# 3_ESC_BOARD.net
KiCad netlist of a schematic drawn in EAGLE
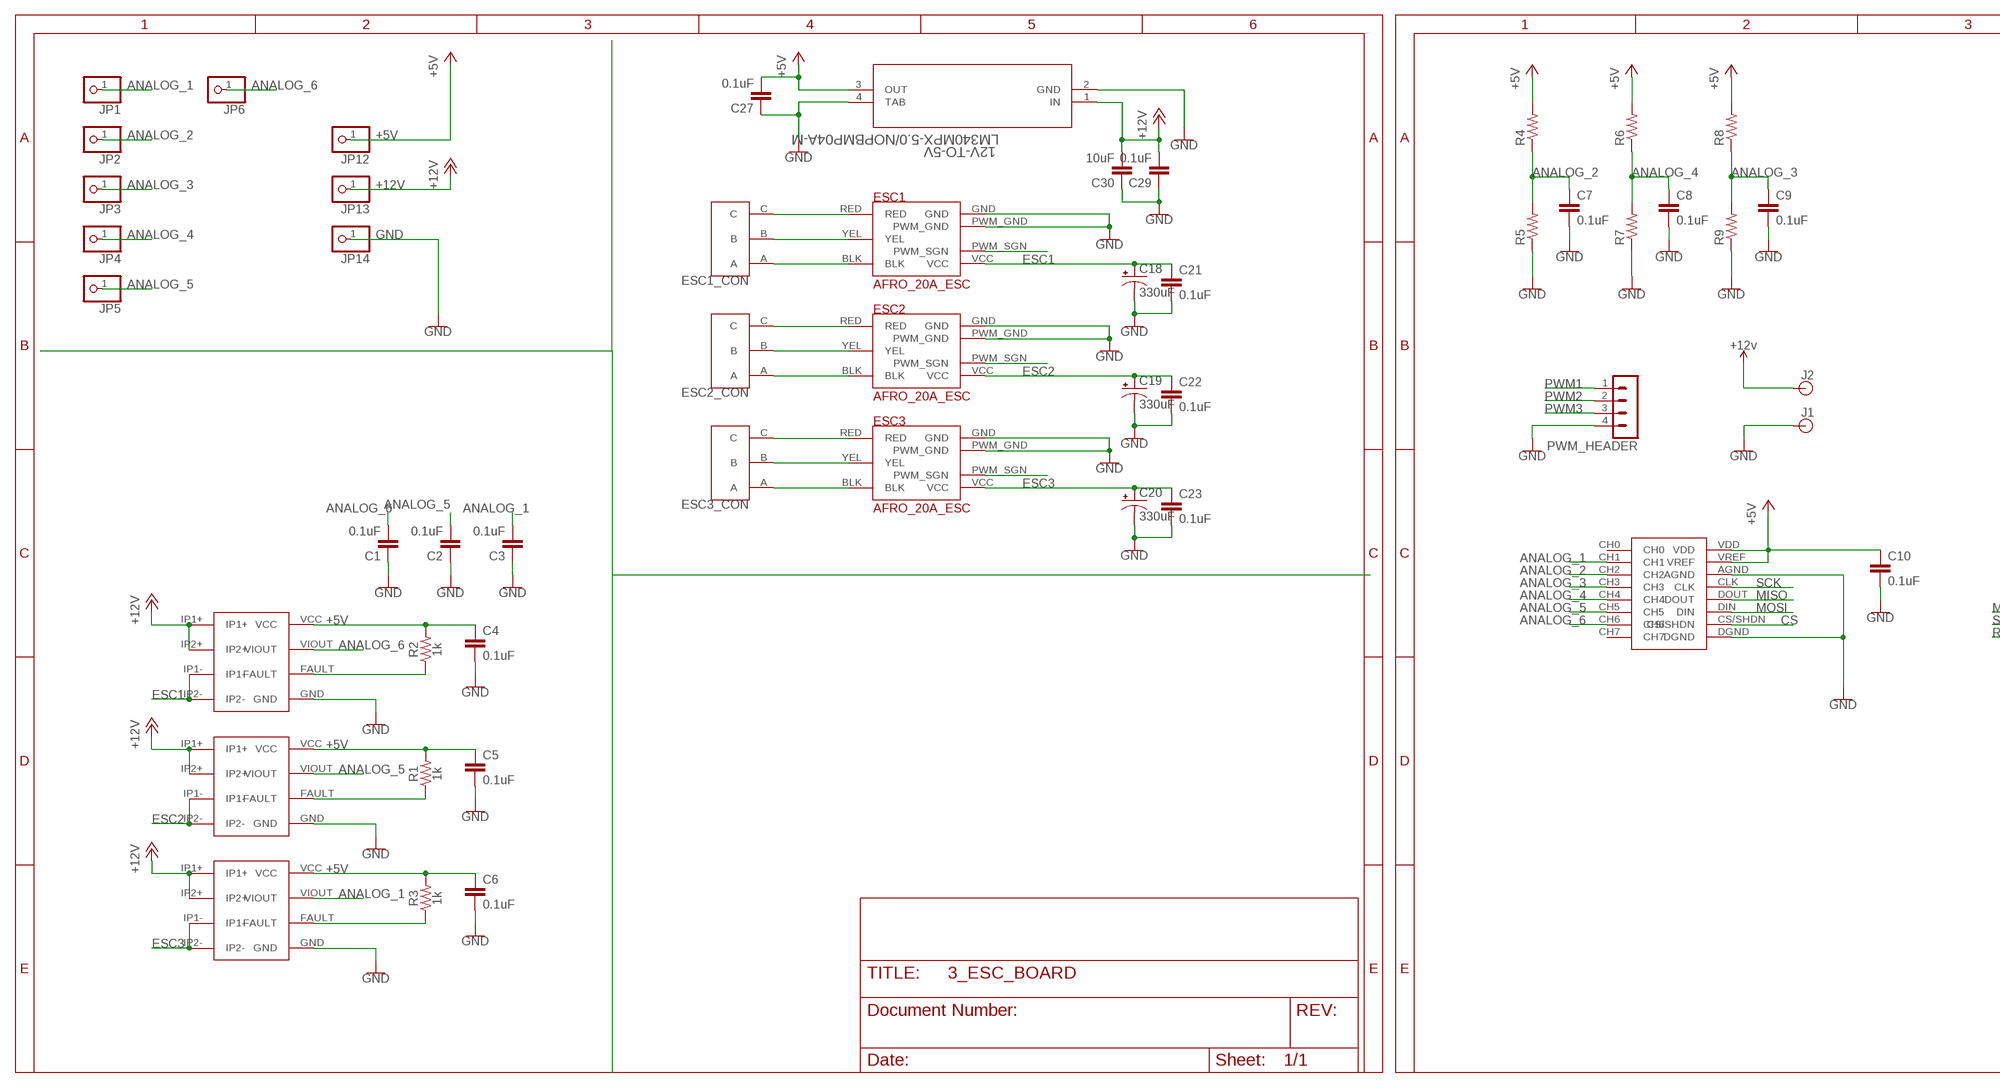
[diagram p0: schematic, sheet 1, part 1 of 3]
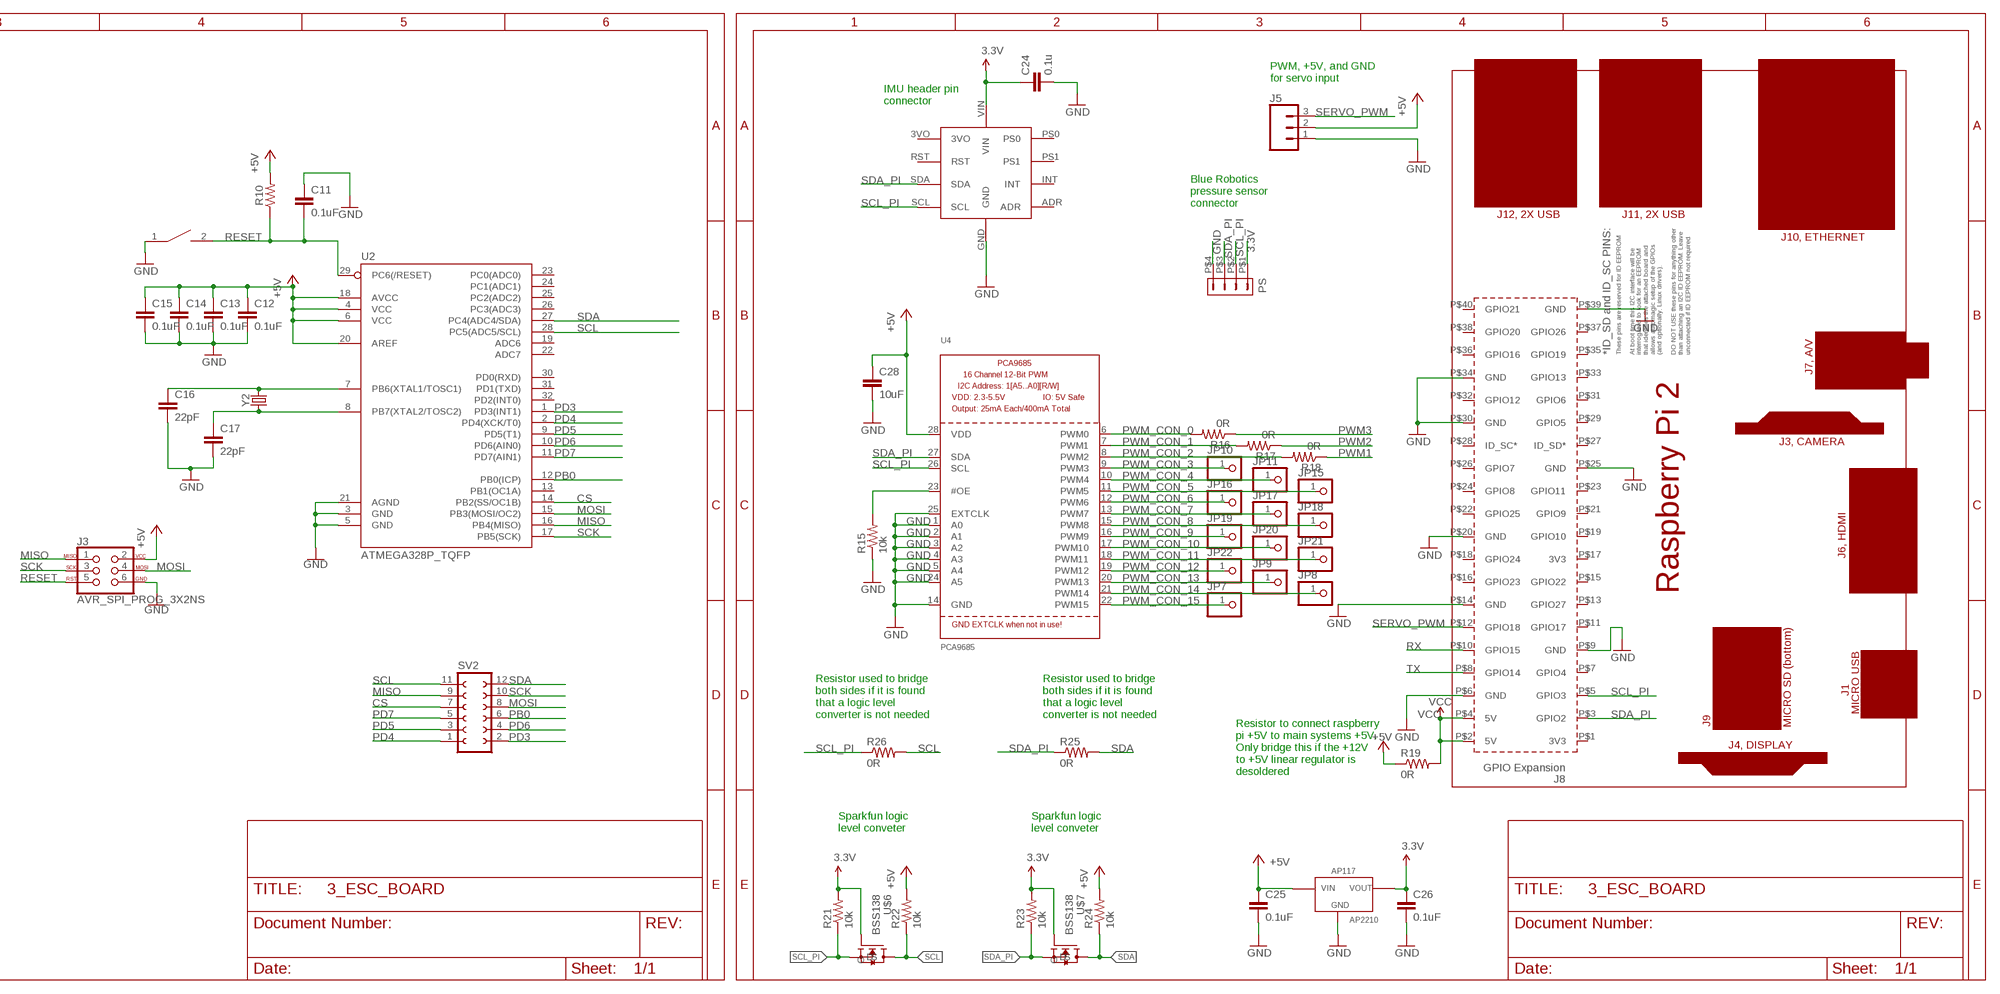
[diagram p1: schematic, sheet 1, part 2 of 3]
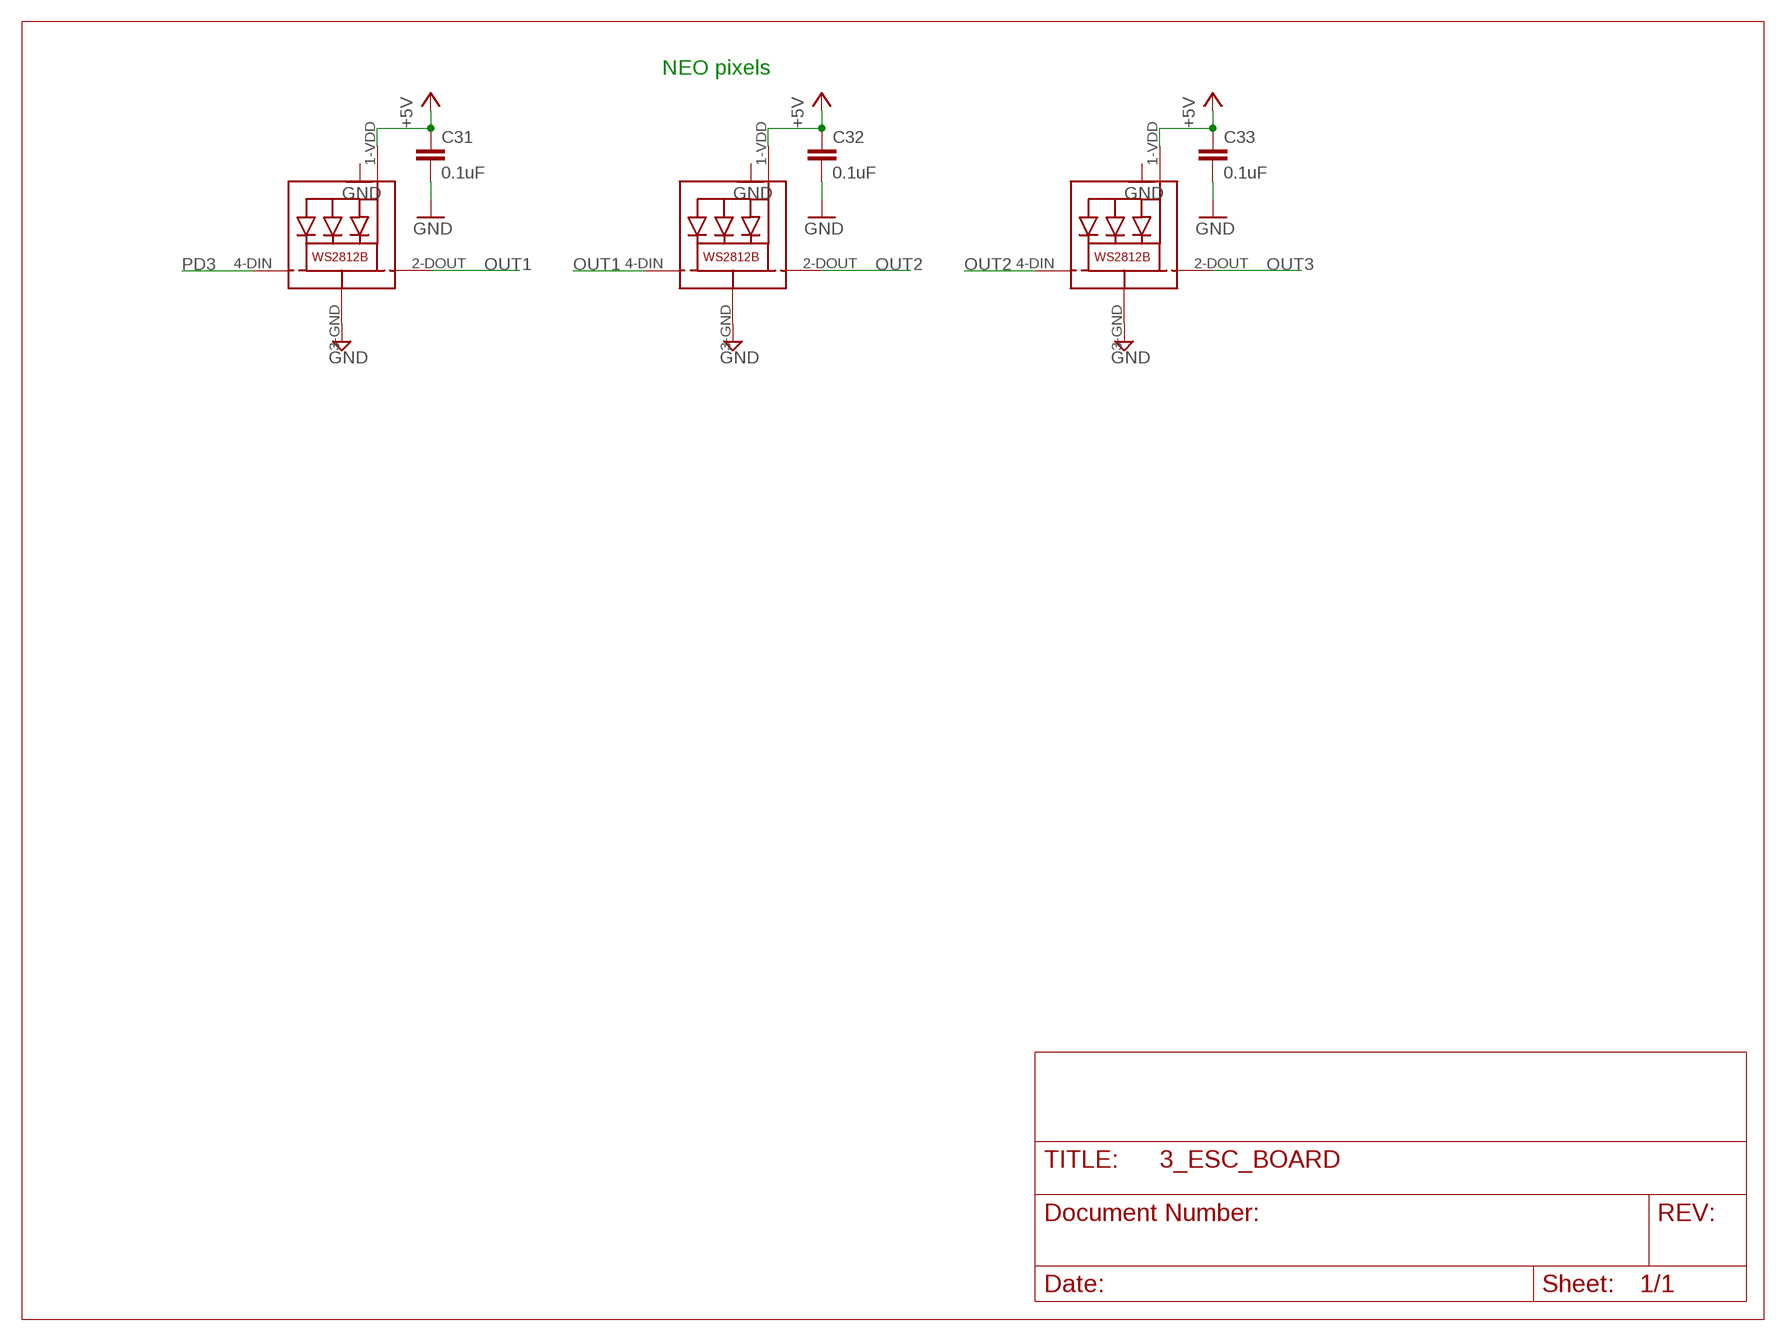
[diagram p2: schematic, sheet 1, part 3 of 3]

(export (version "E")
  (design (tool "Eeschema 10.0.6"))
  (components
    (comp (ref "12V-TO-5V")
      (value "LM340MPX-5.0/NOPBMP04A-M")
      (footprint "eagle-import:MP04A-M")
      (fields (field (name "MANUFACTURER_PART_NUMBER") "LM340MPX5.0NOPB"))
      (libsource (lib "eagle-import") (part "LM340MPX-5.0/NOPBMP04A-M"))
    )
    (comp (ref "C1")
      (value "0.1uF")
      (footprint "eagle-import:0603")
      (libsource (lib "eagle-import") (part "0.1UF-0603-25V-(+80/-20%)"))
    )
    (comp (ref "C2")
      (value "0.1uF")
      (footprint "eagle-import:0603")
      (libsource (lib "eagle-import") (part "0.1UF-0603-25V-(+80/-20%)"))
    )
    (comp (ref "C3")
      (value "0.1uF")
      (footprint "eagle-import:0603")
      (libsource (lib "eagle-import") (part "0.1UF-0603-25V-(+80/-20%)"))
    )
    (comp (ref "C4")
      (value "0.1uF")
      (footprint "eagle-import:0603")
      (libsource (lib "eagle-import") (part "0.1UF-0603-25V-(+80/-20%)"))
    )
    (comp (ref "C5")
      (value "0.1uF")
      (footprint "eagle-import:0603")
      (libsource (lib "eagle-import") (part "0.1UF-0603-25V-(+80/-20%)"))
    )
    (comp (ref "C6")
      (value "0.1uF")
      (footprint "eagle-import:0603")
      (libsource (lib "eagle-import") (part "0.1UF-0603-25V-(+80/-20%)"))
    )
    (comp (ref "C7")
      (value "0.1uF")
      (footprint "eagle-import:0603")
      (libsource (lib "eagle-import") (part "0.1UF-0603-25V-(+80/-20%)"))
    )
    (comp (ref "C8")
      (value "0.1uF")
      (footprint "eagle-import:0603")
      (libsource (lib "eagle-import") (part "0.1UF-0603-25V-(+80/-20%)"))
    )
    (comp (ref "C9")
      (value "0.1uF")
      (footprint "eagle-import:0603")
      (libsource (lib "eagle-import") (part "0.1UF-0603-25V-(+80/-20%)"))
    )
    (comp (ref "C10")
      (value "0.1uF")
      (footprint "eagle-import:0603")
      (libsource (lib "eagle-import") (part "0.1UF-0603-25V-(+80/-20%)"))
    )
    (comp (ref "C11")
      (value "0.1uF")
      (footprint "eagle-import:C0603")
      (libsource (lib "eagle-import") (part "C-EUC0603"))
    )
    (comp (ref "C12")
      (value "0.1uF")
      (footprint "eagle-import:C0603")
      (libsource (lib "eagle-import") (part "C-EUC0603"))
    )
    (comp (ref "C13")
      (value "0.1uF")
      (footprint "eagle-import:C0603")
      (libsource (lib "eagle-import") (part "C-EUC0603"))
    )
    (comp (ref "C14")
      (value "0.1uF")
      (footprint "eagle-import:C0603")
      (libsource (lib "eagle-import") (part "C-EUC0603"))
    )
    (comp (ref "C15")
      (value "0.1uF")
      (footprint "eagle-import:C0603")
      (libsource (lib "eagle-import") (part "C-EUC0603"))
    )
    (comp (ref "C16")
      (value "22pF")
      (footprint "eagle-import:C0603")
      (libsource (lib "eagle-import") (part "C-EUC0603"))
    )
    (comp (ref "C17")
      (value "22pF")
      (footprint "eagle-import:C0603")
      (libsource (lib "eagle-import") (part "C-EUC0603"))
    )
    (comp (ref "C18")
      (value "330uF")
      (footprint "eagle-import:CPOL-US(10.3_10.3MM)")
      (libsource (lib "eagle-import") (part "C-ALUMINUM(330UF)"))
    )
    (comp (ref "C19")
      (value "330uF")
      (footprint "eagle-import:CPOL-US(10.3_10.3MM)")
      (libsource (lib "eagle-import") (part "C-ALUMINUM(330UF)"))
    )
    (comp (ref "C20")
      (value "330uF")
      (footprint "eagle-import:CPOL-US(10.3_10.3MM)")
      (libsource (lib "eagle-import") (part "C-ALUMINUM(330UF)"))
    )
    (comp (ref "C21")
      (value "0.1uF")
      (footprint "eagle-import:0603")
      (libsource (lib "eagle-import") (part "0.1UF-0603-25V-(+80/-20%)"))
    )
    (comp (ref "C22")
      (value "0.1uF")
      (footprint "eagle-import:0603")
      (libsource (lib "eagle-import") (part "0.1UF-0603-25V-(+80/-20%)"))
    )
    (comp (ref "C23")
      (value "0.1uF")
      (footprint "eagle-import:0603")
      (libsource (lib "eagle-import") (part "0.1UF-0603-25V-(+80/-20%)"))
    )
    (comp (ref "C24")
      (value "0.1u")
      (footprint "eagle-import:0603-CAP")
      (libsource (lib "eagle-import") (part "CAP0603-CAP"))
    )
    (comp (ref "C25")
      (value "0.1uF")
      (footprint "eagle-import:0603")
      (libsource (lib "eagle-import") (part "0.1UF-0603-25V-(+80/-20%)"))
    )
    (comp (ref "C26")
      (value "0.1uF")
      (footprint "eagle-import:0603")
      (libsource (lib "eagle-import") (part "0.1UF-0603-25V-(+80/-20%)"))
    )
    (comp (ref "C27")
      (value "0.1uF")
      (footprint "eagle-import:0603")
      (libsource (lib "eagle-import") (part "0.1UF-0603-25V-(+80/-20%)"))
    )
    (comp (ref "C28")
      (value "10uF")
      (footprint "eagle-import:0603-CAP")
      (libsource (lib "eagle-import") (part "0.1UF-25V(+80/-20%)(0603)"))
    )
    (comp (ref "C29")
      (value "0.1uF")
      (footprint "eagle-import:0603")
      (libsource (lib "eagle-import") (part "0.1UF-0603-25V-(+80/-20%)"))
    )
    (comp (ref "C30")
      (value "10uF")
      (footprint "eagle-import:0603")
      (libsource (lib "eagle-import") (part "0.1UF-0603-25V-(+80/-20%)"))
    )
    (comp (ref "C31")
      (value "0.1uF")
      (footprint "eagle-import:C0603")
      (libsource (lib "eagle-import") (part "C-EUC0603"))
    )
    (comp (ref "C32")
      (value "0.1uF")
      (footprint "eagle-import:C0603")
      (libsource (lib "eagle-import") (part "C-EUC0603"))
    )
    (comp (ref "C33")
      (value "0.1uF")
      (footprint "eagle-import:C0603")
      (libsource (lib "eagle-import") (part "C-EUC0603"))
    )
    (comp (ref "ESC1")
      (value "AFRO_20A_ESC")
      (footprint "eagle-import:AFRO_20A_ESC")
      (libsource (lib "eagle-import") (part "AFRO_20A_ESC"))
    )
    (comp (ref "ESC1_CON")
      (value "3PINCONNECTOR")
      (footprint "eagle-import:3PINCONNECTOR")
      (libsource (lib "eagle-import") (part "3PINCONNECTOR"))
    )
    (comp (ref "ESC2")
      (value "AFRO_20A_ESC")
      (footprint "eagle-import:AFRO_20A_ESC")
      (libsource (lib "eagle-import") (part "AFRO_20A_ESC"))
    )
    (comp (ref "ESC2_CON")
      (value "3PINCONNECTOR")
      (footprint "eagle-import:3PINCONNECTOR")
      (libsource (lib "eagle-import") (part "3PINCONNECTOR"))
    )
    (comp (ref "ESC3")
      (value "AFRO_20A_ESC")
      (footprint "eagle-import:AFRO_20A_ESC")
      (libsource (lib "eagle-import") (part "AFRO_20A_ESC"))
    )
    (comp (ref "ESC3_CON")
      (value "3PINCONNECTOR")
      (footprint "eagle-import:3PINCONNECTOR")
      (libsource (lib "eagle-import") (part "3PINCONNECTOR"))
    )
    (comp (ref "J1")
      (value "BANANA_CONN")
      (footprint "eagle-import:BANANA_CONN")
      (libsource (lib "eagle-import") (part "BANANA_CONN"))
    )
    (comp (ref "J2")
      (value "BANANA_CONN")
      (footprint "eagle-import:BANANA_CONN")
      (libsource (lib "eagle-import") (part "BANANA_CONN"))
    )
    (comp (ref "J3")
      (value "AVR_SPI_PROG_3X2NS")
      (footprint "eagle-import:2X3-NS")
      (libsource (lib "eagle-import") (part "AVR_SPI_PROG_3X2NS"))
    )
    (comp (ref "J5")
      (value "CONN_03")
      (footprint "eagle-import:1X03")
      (libsource (lib "eagle-import") (part "CONN_03"))
    )
    (comp (ref "JP1")
      (value "PINHD-1X1")
      (footprint "eagle-import:1X01")
      (libsource (lib "eagle-import") (part "PINHD-1X1"))
    )
    (comp (ref "JP2")
      (value "PINHD-1X1")
      (footprint "eagle-import:1X01")
      (libsource (lib "eagle-import") (part "PINHD-1X1"))
    )
    (comp (ref "JP3")
      (value "PINHD-1X1")
      (footprint "eagle-import:1X01")
      (libsource (lib "eagle-import") (part "PINHD-1X1"))
    )
    (comp (ref "JP4")
      (value "PINHD-1X1")
      (footprint "eagle-import:1X01")
      (libsource (lib "eagle-import") (part "PINHD-1X1"))
    )
    (comp (ref "JP5")
      (value "PINHD-1X1")
      (footprint "eagle-import:1X01")
      (libsource (lib "eagle-import") (part "PINHD-1X1"))
    )
    (comp (ref "JP6")
      (value "PINHD-1X1")
      (footprint "eagle-import:1X01")
      (libsource (lib "eagle-import") (part "PINHD-1X1"))
    )
    (comp (ref "JP7")
      (value "PINHD-1X1")
      (footprint "eagle-import:1X01")
      (libsource (lib "eagle-import") (part "PINHD-1X1"))
    )
    (comp (ref "JP8")
      (value "PINHD-1X1")
      (footprint "eagle-import:1X01")
      (libsource (lib "eagle-import") (part "PINHD-1X1"))
    )
    (comp (ref "JP9")
      (value "PINHD-1X1")
      (footprint "eagle-import:1X01")
      (libsource (lib "eagle-import") (part "PINHD-1X1"))
    )
    (comp (ref "JP10")
      (value "PINHD-1X1")
      (footprint "eagle-import:1X01")
      (libsource (lib "eagle-import") (part "PINHD-1X1"))
    )
    (comp (ref "JP11")
      (value "PINHD-1X1")
      (footprint "eagle-import:1X01")
      (libsource (lib "eagle-import") (part "PINHD-1X1"))
    )
    (comp (ref "JP12")
      (value "PINHD-1X1")
      (footprint "eagle-import:1X01")
      (libsource (lib "eagle-import") (part "PINHD-1X1"))
    )
    (comp (ref "JP13")
      (value "PINHD-1X1")
      (footprint "eagle-import:1X01")
      (libsource (lib "eagle-import") (part "PINHD-1X1"))
    )
    (comp (ref "JP14")
      (value "PINHD-1X1")
      (footprint "eagle-import:1X01")
      (libsource (lib "eagle-import") (part "PINHD-1X1"))
    )
    (comp (ref "JP15")
      (value "PINHD-1X1")
      (footprint "eagle-import:1X01")
      (libsource (lib "eagle-import") (part "PINHD-1X1"))
    )
    (comp (ref "JP16")
      (value "PINHD-1X1")
      (footprint "eagle-import:1X01")
      (libsource (lib "eagle-import") (part "PINHD-1X1"))
    )
    (comp (ref "JP17")
      (value "PINHD-1X1")
      (footprint "eagle-import:1X01")
      (libsource (lib "eagle-import") (part "PINHD-1X1"))
    )
    (comp (ref "JP18")
      (value "PINHD-1X1")
      (footprint "eagle-import:1X01")
      (libsource (lib "eagle-import") (part "PINHD-1X1"))
    )
    (comp (ref "JP19")
      (value "PINHD-1X1")
      (footprint "eagle-import:1X01")
      (libsource (lib "eagle-import") (part "PINHD-1X1"))
    )
    (comp (ref "JP20")
      (value "PINHD-1X1")
      (footprint "eagle-import:1X01")
      (libsource (lib "eagle-import") (part "PINHD-1X1"))
    )
    (comp (ref "JP21")
      (value "PINHD-1X1")
      (footprint "eagle-import:1X01")
      (libsource (lib "eagle-import") (part "PINHD-1X1"))
    )
    (comp (ref "JP22")
      (value "PINHD-1X1")
      (footprint "eagle-import:1X01")
      (libsource (lib "eagle-import") (part "PINHD-1X1"))
    )
    (comp (ref "LED1")
      (value "WS2812B5050")
      (footprint "eagle-import:WS2812B")
      (libsource (lib "eagle-import") (part "WS2812B5050"))
    )
    (comp (ref "LED2")
      (value "WS2812B5050")
      (footprint "eagle-import:WS2812B")
      (libsource (lib "eagle-import") (part "WS2812B5050"))
    )
    (comp (ref "LED3")
      (value "WS2812B5050")
      (footprint "eagle-import:WS2812B")
      (libsource (lib "eagle-import") (part "WS2812B5050"))
    )
    (comp (ref "PCB1")
      (value "RPI2")
      (footprint "eagle-import:RPI2")
      (libsource (lib "eagle-import") (part "RPI2"))
    )
    (comp (ref "PS")
      (value "DF13-4P-1.25DSA")
      (footprint "eagle-import:DF13-4P-1.25DSA")
      (libsource (lib "eagle-import") (part "DF13-4P-1.25DSA"))
    )
    (comp (ref "PWM_HEADER")
      (value "MA04-1")
      (footprint "eagle-import:MA04-1")
      (libsource (lib "eagle-import") (part "MA04-1"))
    )
    (comp (ref "R1")
      (value "1k")
      (footprint "eagle-import:0603")
      (libsource (lib "eagle-import") (part "1KOHM-0603-1/10W-1%"))
    )
    (comp (ref "R2")
      (value "1k")
      (footprint "eagle-import:0603")
      (libsource (lib "eagle-import") (part "1KOHM-0603-1/10W-1%"))
    )
    (comp (ref "R3")
      (value "1k")
      (footprint "eagle-import:0603")
      (libsource (lib "eagle-import") (part "1KOHM-0603-1/10W-1%"))
    )
    (comp (ref "R4")
      (value "R-US_R0603")
      (footprint "eagle-import:R0603")
      (libsource (lib "eagle-import") (part "R-US_R0603"))
    )
    (comp (ref "R5")
      (value "R-US_R0603")
      (footprint "eagle-import:R0603")
      (libsource (lib "eagle-import") (part "R-US_R0603"))
    )
    (comp (ref "R6")
      (value "R-US_R0603")
      (footprint "eagle-import:R0603")
      (libsource (lib "eagle-import") (part "R-US_R0603"))
    )
    (comp (ref "R7")
      (value "R-US_R0603")
      (footprint "eagle-import:R0603")
      (libsource (lib "eagle-import") (part "R-US_R0603"))
    )
    (comp (ref "R8")
      (value "R-US_R0603")
      (footprint "eagle-import:R0603")
      (libsource (lib "eagle-import") (part "R-US_R0603"))
    )
    (comp (ref "R9")
      (value "R-US_R0603")
      (footprint "eagle-import:R0603")
      (libsource (lib "eagle-import") (part "R-US_R0603"))
    )
    (comp (ref "R10")
      (value "RESISTOR0603")
      (footprint "eagle-import:0603")
      (libsource (lib "eagle-import") (part "RESISTOR0603"))
    )
    (comp (ref "R15")
      (value "10k")
      (footprint "eagle-import:0603-RES")
      (libsource (lib "eagle-import") (part "470OHM1/10W1%(0603)"))
    )
    (comp (ref "R16")
      (value "0R")
      (footprint "eagle-import:0603-RES")
      (libsource (lib "eagle-import") (part "470OHM1/10W1%(0603)"))
    )
    (comp (ref "R17")
      (value "0R")
      (footprint "eagle-import:0603-RES")
      (libsource (lib "eagle-import") (part "470OHM1/10W1%(0603)"))
    )
    (comp (ref "R18")
      (value "0R")
      (footprint "eagle-import:0603-RES")
      (libsource (lib "eagle-import") (part "470OHM1/10W1%(0603)"))
    )
    (comp (ref "R19")
      (value "0R")
      (footprint "eagle-import:0603-RES")
      (libsource (lib "eagle-import") (part "RESISTOR0603-RES"))
    )
    (comp (ref "R21")
      (value "10k")
      (footprint "eagle-import:R0603")
      (libsource (lib "eagle-import") (part "R-US_R0603"))
    )
    (comp (ref "R22")
      (value "10k")
      (footprint "eagle-import:R0603")
      (libsource (lib "eagle-import") (part "R-US_R0603"))
    )
    (comp (ref "R23")
      (value "10k")
      (footprint "eagle-import:R0603")
      (libsource (lib "eagle-import") (part "R-US_R0603"))
    )
    (comp (ref "R24")
      (value "10k")
      (footprint "eagle-import:R0603")
      (libsource (lib "eagle-import") (part "R-US_R0603"))
    )
    (comp (ref "R25")
      (value "0R")
      (footprint "eagle-import:0603-RES")
      (libsource (lib "eagle-import") (part "RESISTOR0603-RES"))
    )
    (comp (ref "R26")
      (value "0R")
      (footprint "eagle-import:0603-RES")
      (libsource (lib "eagle-import") (part "RESISTOR0603-RES"))
    )
    (comp (ref "RESET")
      (value "SWITCH")
      (footprint "eagle-import:SW_2512")
      (libsource (lib "eagle-import") (part "SWITCH"))
    )
    (comp (ref "SV2")
      (value "FE06-2")
      (footprint "eagle-import:FE06-2")
      (libsource (lib "eagle-import") (part "FE06-2"))
    )
    (comp (ref "U$1")
      (value "ACS711")
      (footprint "eagle-import:ACS711")
      (libsource (lib "eagle-import") (part "ACS711"))
    )
    (comp (ref "U$2")
      (value "ACS711")
      (footprint "eagle-import:ACS711")
      (libsource (lib "eagle-import") (part "ACS711"))
    )
    (comp (ref "U$3")
      (value "ACS711")
      (footprint "eagle-import:ACS711")
      (libsource (lib "eagle-import") (part "ACS711"))
    )
    (comp (ref "U$4")
      (value "MCP3008")
      (footprint "eagle-import:MCP3008")
      (libsource (lib "eagle-import") (part "MCP3008"))
    )
    (comp (ref "U$5")
      (value "BNO055_9DOF_BREAKOUT")
      (footprint "eagle-import:BNO055")
      (libsource (lib "eagle-import") (part "BNO055_9DOF_BREAKOUT"))
    )
    (comp (ref "U$6")
      (value "BSS138")
      (footprint "eagle-import:BSS138")
      (libsource (lib "eagle-import") (part "BSS138"))
    )
    (comp (ref "U$7")
      (value "BSS138")
      (footprint "eagle-import:BSS138")
      (libsource (lib "eagle-import") (part "BSS138"))
    )
    (comp (ref "U$8")
      (value "AP2210")
      (footprint "eagle-import:SOT-23-3")
      (libsource (lib "eagle-import") (part "AP2210"))
    )
    (comp (ref "U2")
      (value "ATMEGA328P_TQFP")
      (footprint "eagle-import:TQFP32-08")
      (libsource (lib "eagle-import") (part "ATMEGA328P_TQFP"))
    )
    (comp (ref "U4")
      (value "PCA9685")
      (footprint "eagle-import:TSSOP28")
      (libsource (lib "eagle-import") (part "PCA9685"))
    )
    (comp (ref "Y2")
      (value "CRYSTALPTH-HC49US")
      (footprint "eagle-import:HC49US")
      (libsource (lib "eagle-import") (part "CRYSTALPTH-HC49US"))
    )
  )
  (nets
    (net (code "1") (name "+5V") (class "Default")
      (node (ref "12V-TO-5V") (pin "3") (pinfunction "OUT_3") (pintype "power_in"))
      (node (ref "C10") (pin "1") (pinfunction "1_1") (pintype "passive"))
      (node (ref "C12") (pin "1") (pinfunction "1_1") (pintype "passive"))
      (node (ref "C13") (pin "1") (pinfunction "1_1") (pintype "passive"))
      (node (ref "C14") (pin "1") (pinfunction "1_1") (pintype "passive"))
      (node (ref "C15") (pin "1") (pinfunction "1_1") (pintype "passive"))
      (node (ref "C25") (pin "1") (pinfunction "1_1") (pintype "passive"))
      (node (ref "C27") (pin "2") (pinfunction "2_2") (pintype "passive"))
      (node (ref "C28") (pin "1") (pinfunction "1_1") (pintype "passive"))
      (node (ref "C31") (pin "1") (pinfunction "1_1") (pintype "passive"))
      (node (ref "C32") (pin "1") (pinfunction "1_1") (pintype "passive"))
      (node (ref "C33") (pin "1") (pinfunction "1_1") (pintype "passive"))
      (node (ref "C4") (pin "1") (pinfunction "1_1") (pintype "passive"))
      (node (ref "C5") (pin "1") (pinfunction "1_1") (pintype "passive"))
      (node (ref "C6") (pin "1") (pinfunction "1_1") (pintype "passive"))
      (node (ref "J3") (pin "2") (pinfunction "2_2") (pintype "passive"))
      (node (ref "J5") (pin "2") (pinfunction "2_2") (pintype "passive"))
      (node (ref "JP12") (pin "1") (pinfunction "1_1") (pintype "passive"))
      (node (ref "LED1") (pin "1-VDD") (pinfunction "VDD_1-VDD") (pintype "power_in"))
      (node (ref "LED2") (pin "1-VDD") (pinfunction "VDD_1-VDD") (pintype "power_in"))
      (node (ref "LED3") (pin "1-VDD") (pinfunction "VDD_1-VDD") (pintype "power_in"))
      (node (ref "R1") (pin "2") (pinfunction "2_2") (pintype "passive"))
      (node (ref "R10") (pin "2") (pinfunction "2_2") (pintype "passive"))
      (node (ref "R19") (pin "1") (pinfunction "1_1") (pintype "passive"))
      (node (ref "R2") (pin "2") (pinfunction "2_2") (pintype "passive"))
      (node (ref "R22") (pin "2") (pinfunction "2_2") (pintype "passive"))
      (node (ref "R24") (pin "2") (pinfunction "2_2") (pintype "passive"))
      (node (ref "R3") (pin "2") (pinfunction "2_2") (pintype "passive"))
      (node (ref "R4") (pin "2") (pinfunction "2_2") (pintype "passive"))
      (node (ref "R6") (pin "2") (pinfunction "2_2") (pintype "passive"))
      (node (ref "R8") (pin "2") (pinfunction "2_2") (pintype "passive"))
      (node (ref "U$1") (pin "VCC") (pinfunction "VCC_VCC") (pintype "bidirectional"))
      (node (ref "U$2") (pin "VCC") (pinfunction "VCC_VCC") (pintype "bidirectional"))
      (node (ref "U$3") (pin "VCC") (pinfunction "VCC_VCC") (pintype "bidirectional"))
      (node (ref "U$4") (pin "VDD") (pinfunction "VDD_VDD") (pintype "bidirectional"))
      (node (ref "U$4") (pin "VREF") (pinfunction "VREF_VREF") (pintype "bidirectional"))
      (node (ref "U$8") (pin "VIN") (pinfunction "VIN_VIN") (pintype "input"))
      (node (ref "U2") (pin "18") (pinfunction "AVCC_18") (pintype "bidirectional"))
      (node (ref "U2") (pin "20") (pinfunction "AREF_20") (pintype "bidirectional"))
      (node (ref "U2") (pin "4") (pinfunction "VCC_4") (pintype "bidirectional"))
      (node (ref "U2") (pin "6") (pinfunction "VCC_6") (pintype "bidirectional"))
      (node (ref "U4") (pin "28") (pinfunction "VDD_28") (pintype "power_in"))
    )
    (net (code "2") (name "+12V") (class "Default")
      (node (ref "12V-TO-5V") (pin "1") (pinfunction "IN_1") (pintype "power_in"))
      (node (ref "C29") (pin "2") (pinfunction "2_2") (pintype "passive"))
      (node (ref "C30") (pin "2") (pinfunction "2_2") (pintype "passive"))
      (node (ref "J2") (pin "P$1") (pinfunction "1_P$1") (pintype "passive"))
      (node (ref "JP13") (pin "1") (pinfunction "1_1") (pintype "passive"))
      (node (ref "U$1") (pin "IP1+") (pinfunction "IP1+_IP1+") (pintype "bidirectional"))
      (node (ref "U$1") (pin "IP2+") (pinfunction "IP2+_IP2+") (pintype "bidirectional"))
      (node (ref "U$2") (pin "IP1+") (pinfunction "IP1+_IP1+") (pintype "bidirectional"))
      (node (ref "U$2") (pin "IP2+") (pinfunction "IP2+_IP2+") (pintype "bidirectional"))
      (node (ref "U$3") (pin "IP1+") (pinfunction "IP1+_IP1+") (pintype "bidirectional"))
      (node (ref "U$3") (pin "IP2+") (pinfunction "IP2+_IP2+") (pintype "bidirectional"))
    )
    (net (code "3") (name "/ANALOG_1") (class "Default")
      (node (ref "C3") (pin "2") (pinfunction "2_2") (pintype "passive"))
      (node (ref "JP1") (pin "1") (pinfunction "1_1") (pintype "passive"))
      (node (ref "U$3") (pin "VIOUT") (pinfunction "VIOUT_VIOUT") (pintype "bidirectional"))
      (node (ref "U$4") (pin "CH1") (pinfunction "CH1_CH1") (pintype "bidirectional"))
    )
    (net (code "4") (name "/ANALOG_2") (class "Default")
      (node (ref "C7") (pin "1") (pinfunction "1_1") (pintype "passive"))
      (node (ref "JP2") (pin "1") (pinfunction "1_1") (pintype "passive"))
      (node (ref "R4") (pin "1") (pinfunction "1_1") (pintype "passive"))
      (node (ref "R5") (pin "2") (pinfunction "2_2") (pintype "passive"))
      (node (ref "U$4") (pin "CH2") (pinfunction "CH2_CH2") (pintype "bidirectional"))
    )
    (net (code "5") (name "/ANALOG_3") (class "Default")
      (node (ref "C9") (pin "1") (pinfunction "1_1") (pintype "passive"))
      (node (ref "JP3") (pin "1") (pinfunction "1_1") (pintype "passive"))
      (node (ref "R8") (pin "1") (pinfunction "1_1") (pintype "passive"))
      (node (ref "R9") (pin "2") (pinfunction "2_2") (pintype "passive"))
      (node (ref "U$4") (pin "CH3") (pinfunction "CH3_CH3") (pintype "bidirectional"))
    )
    (net (code "6") (name "/ANALOG_4") (class "Default")
      (node (ref "C8") (pin "1") (pinfunction "1_1") (pintype "passive"))
      (node (ref "JP4") (pin "1") (pinfunction "1_1") (pintype "passive"))
      (node (ref "R6") (pin "1") (pinfunction "1_1") (pintype "passive"))
      (node (ref "R7") (pin "2") (pinfunction "2_2") (pintype "passive"))
      (node (ref "U$4") (pin "CH4") (pinfunction "CH4_CH4") (pintype "bidirectional"))
    )
    (net (code "7") (name "/ANALOG_5") (class "Default")
      (node (ref "C2") (pin "2") (pinfunction "2_2") (pintype "passive"))
      (node (ref "JP5") (pin "1") (pinfunction "1_1") (pintype "passive"))
      (node (ref "U$2") (pin "VIOUT") (pinfunction "VIOUT_VIOUT") (pintype "bidirectional"))
      (node (ref "U$4") (pin "CH5") (pinfunction "CH5_CH5") (pintype "bidirectional"))
    )
    (net (code "8") (name "/ANALOG_6") (class "Default")
      (node (ref "C1") (pin "2") (pinfunction "2_2") (pintype "passive"))
      (node (ref "JP6") (pin "1") (pinfunction "1_1") (pintype "passive"))
      (node (ref "U$1") (pin "VIOUT") (pinfunction "VIOUT_VIOUT") (pintype "bidirectional"))
      (node (ref "U$4") (pin "CH6") (pinfunction "CH6_CH6") (pintype "bidirectional"))
    )
    (net (code "9") (name "/CS") (class "Default")
      (node (ref "SV2") (pin "7") (pinfunction "7_7") (pintype "passive"))
      (node (ref "U$4") (pin "CS/SHDN") (pinfunction "CS/SHDN_CS/SHDN") (pintype "bidirectional"))
      (node (ref "U2") (pin "14") (pinfunction "PB2(SS/OC1B)_14") (pintype "bidirectional"))
    )
    (net (code "10") (name "/ESC1") (class "Default")
      (node (ref "C18") (pin "+") (pinfunction "+_+") (pintype "passive"))
      (node (ref "C21") (pin "1") (pinfunction "1_1") (pintype "passive"))
      (node (ref "ESC1") (pin "VCC") (pinfunction "VCC_VCC") (pintype "bidirectional"))
      (node (ref "U$1") (pin "IP1-") (pinfunction "IP1-_IP1-") (pintype "bidirectional"))
      (node (ref "U$1") (pin "IP2-") (pinfunction "IP2-_IP2-") (pintype "bidirectional"))
    )
    (net (code "11") (name "/ESC2") (class "Default")
      (node (ref "C19") (pin "+") (pinfunction "+_+") (pintype "passive"))
      (node (ref "C22") (pin "1") (pinfunction "1_1") (pintype "passive"))
      (node (ref "ESC2") (pin "VCC") (pinfunction "VCC_VCC") (pintype "bidirectional"))
      (node (ref "U$2") (pin "IP1-") (pinfunction "IP1-_IP1-") (pintype "bidirectional"))
      (node (ref "U$2") (pin "IP2-") (pinfunction "IP2-_IP2-") (pintype "bidirectional"))
    )
    (net (code "12") (name "/ESC3") (class "Default")
      (node (ref "C20") (pin "+") (pinfunction "+_+") (pintype "passive"))
      (node (ref "C23") (pin "1") (pinfunction "1_1") (pintype "passive"))
      (node (ref "ESC3") (pin "VCC") (pinfunction "VCC_VCC") (pintype "bidirectional"))
      (node (ref "U$3") (pin "IP1-") (pinfunction "IP1-_IP1-") (pintype "bidirectional"))
      (node (ref "U$3") (pin "IP2-") (pinfunction "IP2-_IP2-") (pintype "bidirectional"))
    )
    (net (code "13") (name "/MISO") (class "Default")
      (node (ref "J3") (pin "1") (pinfunction "1_1") (pintype "passive"))
      (node (ref "SV2") (pin "9") (pinfunction "9_9") (pintype "passive"))
      (node (ref "U$4") (pin "DOUT") (pinfunction "DOUT_DOUT") (pintype "bidirectional"))
      (node (ref "U2") (pin "16") (pinfunction "PB4(MISO)_16") (pintype "bidirectional"))
    )
    (net (code "14") (name "/MOSI") (class "Default")
      (node (ref "J3") (pin "4") (pinfunction "4_4") (pintype "passive"))
      (node (ref "SV2") (pin "8") (pinfunction "8_8") (pintype "passive"))
      (node (ref "U$4") (pin "DIN") (pinfunction "DIN_DIN") (pintype "bidirectional"))
      (node (ref "U2") (pin "15") (pinfunction "PB3(MOSI/OC2)_15") (pintype "bidirectional"))
    )
    (net (code "15") (name "/OUT1") (class "Default")
      (node (ref "LED1") (pin "2-DOUT") (pinfunction "DO_2-DOUT") (pintype "output"))
      (node (ref "LED2") (pin "4-DIN") (pinfunction "DI_4-DIN") (pintype "input"))
    )
    (net (code "16") (name "/OUT2") (class "Default")
      (node (ref "LED2") (pin "2-DOUT") (pinfunction "DO_2-DOUT") (pintype "output"))
      (node (ref "LED3") (pin "4-DIN") (pinfunction "DI_4-DIN") (pintype "input"))
    )
    (net (code "17") (name "/OUT3") (class "Default")
      (node (ref "LED3") (pin "2-DOUT") (pinfunction "DO_2-DOUT") (pintype "output"))
    )
    (net (code "18") (name "/PB0") (class "Default")
      (node (ref "SV2") (pin "6") (pinfunction "6_6") (pintype "passive"))
      (node (ref "U2") (pin "12") (pinfunction "PB0(ICP)_12") (pintype "bidirectional"))
    )
    (net (code "19") (name "/PD3") (class "Default")
      (node (ref "LED1") (pin "4-DIN") (pinfunction "DI_4-DIN") (pintype "input"))
      (node (ref "SV2") (pin "2") (pinfunction "2_2") (pintype "passive"))
      (node (ref "U2") (pin "1") (pinfunction "PD3(INT1)_1") (pintype "bidirectional"))
    )
    (net (code "20") (name "/PD4") (class "Default")
      (node (ref "SV2") (pin "1") (pinfunction "1_1") (pintype "passive"))
      (node (ref "U2") (pin "2") (pinfunction "PD4(XCK/T0)_2") (pintype "bidirectional"))
    )
    (net (code "21") (name "/PD5") (class "Default")
      (node (ref "SV2") (pin "3") (pinfunction "3_3") (pintype "passive"))
      (node (ref "U2") (pin "9") (pinfunction "PD5(T1)_9") (pintype "bidirectional"))
    )
    (net (code "22") (name "/PD6") (class "Default")
      (node (ref "SV2") (pin "4") (pinfunction "4_4") (pintype "passive"))
      (node (ref "U2") (pin "10") (pinfunction "PD6(AIN0)_10") (pintype "bidirectional"))
    )
    (net (code "23") (name "/PD7") (class "Default")
      (node (ref "SV2") (pin "5") (pinfunction "5_5") (pintype "passive"))
      (node (ref "U2") (pin "11") (pinfunction "PD7(AIN1)_11") (pintype "bidirectional"))
    )
    (net (code "24") (name "/PWM1") (class "Default")
      (node (ref "ESC1") (pin "PWM_SGN") (pinfunction "PWM_SGN_PWM_SGN") (pintype "bidirectional"))
      (node (ref "PWM_HEADER") (pin "1") (pinfunction "1_1") (pintype "passive"))
      (node (ref "R18") (pin "1") (pinfunction "1_1") (pintype "passive"))
    )
    (net (code "25") (name "/PWM2") (class "Default")
      (node (ref "ESC2") (pin "PWM_SGN") (pinfunction "PWM_SGN_PWM_SGN") (pintype "bidirectional"))
      (node (ref "PWM_HEADER") (pin "2") (pinfunction "2_2") (pintype "passive"))
      (node (ref "R17") (pin "1") (pinfunction "1_1") (pintype "passive"))
    )
    (net (code "26") (name "/PWM3") (class "Default")
      (node (ref "ESC3") (pin "PWM_SGN") (pinfunction "PWM_SGN_PWM_SGN") (pintype "bidirectional"))
      (node (ref "PWM_HEADER") (pin "3") (pinfunction "3_3") (pintype "passive"))
      (node (ref "R16") (pin "1") (pinfunction "1_1") (pintype "passive"))
    )
    (net (code "27") (name "/PWM_CON_0") (class "Default")
      (node (ref "R16") (pin "2") (pinfunction "2_2") (pintype "passive"))
      (node (ref "U4") (pin "6") (pinfunction "PWM0_6") (pintype "output"))
    )
    (net (code "28") (name "/PWM_CON_1") (class "Default")
      (node (ref "R17") (pin "2") (pinfunction "2_2") (pintype "passive"))
      (node (ref "U4") (pin "7") (pinfunction "PWM1_7") (pintype "output"))
    )
    (net (code "29") (name "/PWM_CON_2") (class "Default")
      (node (ref "R18") (pin "2") (pinfunction "2_2") (pintype "passive"))
      (node (ref "U4") (pin "8") (pinfunction "PWM2_8") (pintype "output"))
    )
    (net (code "30") (name "/PWM_CON_3") (class "Default")
      (node (ref "JP10") (pin "1") (pinfunction "1_1") (pintype "passive"))
      (node (ref "U4") (pin "9") (pinfunction "PWM3_9") (pintype "output"))
    )
    (net (code "31") (name "/PWM_CON_4") (class "Default")
      (node (ref "JP11") (pin "1") (pinfunction "1_1") (pintype "passive"))
      (node (ref "U4") (pin "10") (pinfunction "PWM4_10") (pintype "output"))
    )
    (net (code "32") (name "/PWM_CON_5") (class "Default")
      (node (ref "JP15") (pin "1") (pinfunction "1_1") (pintype "passive"))
      (node (ref "U4") (pin "11") (pinfunction "PWM5_11") (pintype "output"))
    )
    (net (code "33") (name "/PWM_CON_6") (class "Default")
      (node (ref "JP16") (pin "1") (pinfunction "1_1") (pintype "passive"))
      (node (ref "U4") (pin "12") (pinfunction "PWM6_12") (pintype "output"))
    )
    (net (code "34") (name "/PWM_CON_7") (class "Default")
      (node (ref "JP17") (pin "1") (pinfunction "1_1") (pintype "passive"))
      (node (ref "U4") (pin "13") (pinfunction "PWM7_13") (pintype "output"))
    )
    (net (code "35") (name "/PWM_CON_8") (class "Default")
      (node (ref "JP18") (pin "1") (pinfunction "1_1") (pintype "passive"))
      (node (ref "U4") (pin "15") (pinfunction "PWM8_15") (pintype "output"))
    )
    (net (code "36") (name "/PWM_CON_9") (class "Default")
      (node (ref "JP19") (pin "1") (pinfunction "1_1") (pintype "passive"))
      (node (ref "U4") (pin "16") (pinfunction "PWM9_16") (pintype "output"))
    )
    (net (code "37") (name "/PWM_CON_10") (class "Default")
      (node (ref "JP20") (pin "1") (pinfunction "1_1") (pintype "passive"))
      (node (ref "U4") (pin "17") (pinfunction "PWM10_17") (pintype "output"))
    )
    (net (code "38") (name "/PWM_CON_11") (class "Default")
      (node (ref "JP21") (pin "1") (pinfunction "1_1") (pintype "passive"))
      (node (ref "U4") (pin "18") (pinfunction "PWM11_18") (pintype "output"))
    )
    (net (code "39") (name "/PWM_CON_12") (class "Default")
      (node (ref "JP22") (pin "1") (pinfunction "1_1") (pintype "passive"))
      (node (ref "U4") (pin "19") (pinfunction "PWM12_19") (pintype "output"))
    )
    (net (code "40") (name "/PWM_CON_13") (class "Default")
      (node (ref "JP9") (pin "1") (pinfunction "1_1") (pintype "passive"))
      (node (ref "U4") (pin "20") (pinfunction "PWM13_20") (pintype "output"))
    )
    (net (code "41") (name "/PWM_CON_14") (class "Default")
      (node (ref "JP8") (pin "1") (pinfunction "1_1") (pintype "passive"))
      (node (ref "U4") (pin "21") (pinfunction "PWM14_21") (pintype "output"))
    )
    (net (code "42") (name "/PWM_CON_15") (class "Default")
      (node (ref "JP7") (pin "1") (pinfunction "1_1") (pintype "passive"))
      (node (ref "U4") (pin "22") (pinfunction "PWM15_22") (pintype "output"))
    )
    (net (code "43") (name "/RESET") (class "Default")
      (node (ref "C11") (pin "2") (pinfunction "2_2") (pintype "passive"))
      (node (ref "J3") (pin "5") (pinfunction "5_5") (pintype "passive"))
      (node (ref "R10") (pin "1") (pinfunction "1_1") (pintype "passive"))
      (node (ref "RESET") (pin "2") (pinfunction "P$2_2") (pintype "bidirectional"))
      (node (ref "U2") (pin "29") (pinfunction "PC6(/RESET)_29") (pintype "bidirectional"))
    )
    (net (code "44") (name "/RX") (class "Default")
      (node (ref "PCB1") (pin "P$10") (pinfunction "GPIO15_P$10") (pintype "bidirectional"))
    )
    (net (code "45") (name "/SCK") (class "Default")
      (node (ref "J3") (pin "3") (pinfunction "3_3") (pintype "passive"))
      (node (ref "SV2") (pin "10") (pinfunction "10_10") (pintype "passive"))
      (node (ref "U$4") (pin "CLK") (pinfunction "CLK_CLK") (pintype "bidirectional"))
      (node (ref "U2") (pin "17") (pinfunction "PB5(SCK)_17") (pintype "bidirectional"))
    )
    (net (code "46") (name "/SERVO_PWM") (class "Default")
      (node (ref "J5") (pin "3") (pinfunction "3_3") (pintype "passive"))
      (node (ref "PCB1") (pin "P$12") (pinfunction "GPIO18_P$12") (pintype "bidirectional"))
    )
    (net (code "47") (name "/TX") (class "Default")
      (node (ref "PCB1") (pin "P$8") (pinfunction "GPIO14_P$8") (pintype "bidirectional"))
    )
    (net (code "48") (name "3.3V") (class "Default")
      (node (ref "C24") (pin "1") (pinfunction "1_1") (pintype "passive"))
      (node (ref "C26") (pin "1") (pinfunction "1_1") (pintype "passive"))
      (node (ref "PS") (pin "P$1") (pinfunction "1_P$1") (pintype "passive"))
      (node (ref "R21") (pin "2") (pinfunction "2_2") (pintype "passive"))
      (node (ref "R23") (pin "2") (pinfunction "2_2") (pintype "passive"))
      (node (ref "U$5") (pin "VIN") (pinfunction "VIN_VIN") (pintype "bidirectional"))
      (node (ref "U$6") (pin "G") (pinfunction "G_G") (pintype "passive"))
      (node (ref "U$7") (pin "G") (pinfunction "G_G") (pintype "passive"))
      (node (ref "U$8") (pin "VOUT") (pinfunction "VOUT_VOUT") (pintype "output"))
    )
    (net (code "49") (name "GND") (class "Default")
      (node (ref "12V-TO-5V") (pin "2") (pinfunction "GND_2") (pintype "power_in"))
      (node (ref "12V-TO-5V") (pin "4") (pinfunction "TAB_4") (pintype "power_in"))
      (node (ref "C1") (pin "1") (pinfunction "1_1") (pintype "passive"))
      (node (ref "C10") (pin "2") (pinfunction "2_2") (pintype "passive"))
      (node (ref "C11") (pin "1") (pinfunction "1_1") (pintype "passive"))
      (node (ref "C12") (pin "2") (pinfunction "2_2") (pintype "passive"))
      (node (ref "C13") (pin "2") (pinfunction "2_2") (pintype "passive"))
      (node (ref "C14") (pin "2") (pinfunction "2_2") (pintype "passive"))
      (node (ref "C15") (pin "2") (pinfunction "2_2") (pintype "passive"))
      (node (ref "C16") (pin "2") (pinfunction "2_2") (pintype "passive"))
      (node (ref "C17") (pin "2") (pinfunction "2_2") (pintype "passive"))
      (node (ref "C18") (pin "-") (pinfunction "-_-") (pintype "passive"))
      (node (ref "C19") (pin "-") (pinfunction "-_-") (pintype "passive"))
      (node (ref "C2") (pin "1") (pinfunction "1_1") (pintype "passive"))
      (node (ref "C20") (pin "-") (pinfunction "-_-") (pintype "passive"))
      (node (ref "C21") (pin "2") (pinfunction "2_2") (pintype "passive"))
      (node (ref "C22") (pin "2") (pinfunction "2_2") (pintype "passive"))
      (node (ref "C23") (pin "2") (pinfunction "2_2") (pintype "passive"))
      (node (ref "C24") (pin "2") (pinfunction "2_2") (pintype "passive"))
      (node (ref "C25") (pin "2") (pinfunction "2_2") (pintype "passive"))
      (node (ref "C26") (pin "2") (pinfunction "2_2") (pintype "passive"))
      (node (ref "C27") (pin "1") (pinfunction "1_1") (pintype "passive"))
      (node (ref "C28") (pin "2") (pinfunction "2_2") (pintype "passive"))
      (node (ref "C29") (pin "1") (pinfunction "1_1") (pintype "passive"))
      (node (ref "C3") (pin "1") (pinfunction "1_1") (pintype "passive"))
      (node (ref "C30") (pin "1") (pinfunction "1_1") (pintype "passive"))
      (node (ref "C31") (pin "2") (pinfunction "2_2") (pintype "passive"))
      (node (ref "C32") (pin "2") (pinfunction "2_2") (pintype "passive"))
      (node (ref "C33") (pin "2") (pinfunction "2_2") (pintype "passive"))
      (node (ref "C4") (pin "2") (pinfunction "2_2") (pintype "passive"))
      (node (ref "C5") (pin "2") (pinfunction "2_2") (pintype "passive"))
      (node (ref "C6") (pin "2") (pinfunction "2_2") (pintype "passive"))
      (node (ref "C7") (pin "2") (pinfunction "2_2") (pintype "passive"))
      (node (ref "C8") (pin "2") (pinfunction "2_2") (pintype "passive"))
      (node (ref "C9") (pin "2") (pinfunction "2_2") (pintype "passive"))
      (node (ref "ESC1") (pin "GND") (pinfunction "GND_GND") (pintype "bidirectional"))
      (node (ref "ESC1") (pin "PWM_GND") (pinfunction "PWM_GND_PWM_GND") (pintype "bidirectional"))
      (node (ref "ESC2") (pin "GND") (pinfunction "GND_GND") (pintype "bidirectional"))
      (node (ref "ESC2") (pin "PWM_GND") (pinfunction "PWM_GND_PWM_GND") (pintype "bidirectional"))
      (node (ref "ESC3") (pin "GND") (pinfunction "GND_GND") (pintype "bidirectional"))
      (node (ref "ESC3") (pin "PWM_GND") (pinfunction "PWM_GND_PWM_GND") (pintype "bidirectional"))
      (node (ref "J1") (pin "P$1") (pinfunction "1_P$1") (pintype "passive"))
      (node (ref "J3") (pin "6") (pinfunction "6_6") (pintype "passive"))
      (node (ref "J5") (pin "1") (pinfunction "1_1") (pintype "passive"))
      (node (ref "JP14") (pin "1") (pinfunction "1_1") (pintype "passive"))
      (node (ref "LED1") (pin "3-GND") (pinfunction "GND_3-GND") (pintype "power_in"))
      (node (ref "LED2") (pin "3-GND") (pinfunction "GND_3-GND") (pintype "power_in"))
      (node (ref "LED3") (pin "3-GND") (pinfunction "GND_3-GND") (pintype "power_in"))
      (node (ref "PCB1") (pin "P$14") (pinfunction "GND_P$14") (pintype "bidirectional"))
      (node (ref "PCB1") (pin "P$20") (pinfunction "GND_P$20") (pintype "bidirectional"))
      (node (ref "PCB1") (pin "P$25") (pinfunction "GND_P$25") (pintype "bidirectional"))
      (node (ref "PCB1") (pin "P$30") (pinfunction "GND_P$30") (pintype "bidirectional"))
      (node (ref "PCB1") (pin "P$34") (pinfunction "GND_P$34") (pintype "bidirectional"))
      (node (ref "PCB1") (pin "P$39") (pinfunction "GND_P$39") (pintype "bidirectional"))
      (node (ref "PCB1") (pin "P$6") (pinfunction "GND_P$6") (pintype "bidirectional"))
      (node (ref "PCB1") (pin "P$9") (pinfunction "GND_P$9") (pintype "bidirectional"))
      (node (ref "PS") (pin "P$4") (pinfunction "4_P$4") (pintype "passive"))
      (node (ref "PWM_HEADER") (pin "4") (pinfunction "4_4") (pintype "passive"))
      (node (ref "R15") (pin "1") (pinfunction "1_1") (pintype "passive"))
      (node (ref "R5") (pin "1") (pinfunction "1_1") (pintype "passive"))
      (node (ref "R7") (pin "1") (pinfunction "1_1") (pintype "passive"))
      (node (ref "R9") (pin "1") (pinfunction "1_1") (pintype "passive"))
      (node (ref "RESET") (pin "1") (pinfunction "P$1_1") (pintype "bidirectional"))
      (node (ref "U$1") (pin "GND") (pinfunction "GND_GND") (pintype "bidirectional"))
      (node (ref "U$2") (pin "GND") (pinfunction "GND_GND") (pintype "bidirectional"))
      (node (ref "U$3") (pin "GND") (pinfunction "GND_GND") (pintype "bidirectional"))
      (node (ref "U$4") (pin "AGND") (pinfunction "AGND_AGND") (pintype "bidirectional"))
      (node (ref "U$4") (pin "DGND") (pinfunction "DGND_DGND") (pintype "bidirectional"))
      (node (ref "U$5") (pin "GND") (pinfunction "GND_GND") (pintype "bidirectional"))
      (node (ref "U$8") (pin "GND") (pinfunction "GND_GND") (pintype "bidirectional"))
      (node (ref "U2") (pin "21") (pinfunction "AGND_21") (pintype "bidirectional"))
      (node (ref "U2") (pin "3") (pinfunction "GND_3") (pintype "bidirectional"))
      (node (ref "U2") (pin "5") (pinfunction "GND_5") (pintype "bidirectional"))
      (node (ref "U4") (pin "1") (pinfunction "A0_1") (pintype "bidirectional"))
      (node (ref "U4") (pin "14") (pinfunction "GND_14") (pintype "power_in"))
      (node (ref "U4") (pin "2") (pinfunction "A1_2") (pintype "bidirectional"))
      (node (ref "U4") (pin "24") (pinfunction "A5_24") (pintype "bidirectional"))
      (node (ref "U4") (pin "25") (pinfunction "EXTCLK_25") (pintype "input"))
      (node (ref "U4") (pin "3") (pinfunction "A2_3") (pintype "bidirectional"))
      (node (ref "U4") (pin "4") (pinfunction "A3_4") (pintype "bidirectional"))
      (node (ref "U4") (pin "5") (pinfunction "A4_5") (pintype "bidirectional"))
    )
    (net (code "50") (name "Net-(ESC1-PadBLK)") (class "Default")
      (node (ref "ESC1") (pin "BLK") (pinfunction "BLK_BLK") (pintype "bidirectional"))
      (node (ref "ESC1_CON") (pin "A") (pinfunction "A_A") (pintype "bidirectional"))
    )
    (net (code "51") (name "Net-(ESC1-PadRED)") (class "Default")
      (node (ref "ESC1") (pin "RED") (pinfunction "RED_RED") (pintype "bidirectional"))
      (node (ref "ESC1_CON") (pin "C") (pinfunction "C_C") (pintype "bidirectional"))
    )
    (net (code "52") (name "Net-(ESC1-PadYEL)") (class "Default")
      (node (ref "ESC1") (pin "YEL") (pinfunction "YEL_YEL") (pintype "bidirectional"))
      (node (ref "ESC1_CON") (pin "B") (pinfunction "B_B") (pintype "bidirectional"))
    )
    (net (code "53") (name "Net-(ESC2-PadBLK)") (class "Default")
      (node (ref "ESC2") (pin "BLK") (pinfunction "BLK_BLK") (pintype "bidirectional"))
      (node (ref "ESC2_CON") (pin "A") (pinfunction "A_A") (pintype "bidirectional"))
    )
    (net (code "54") (name "Net-(ESC2-PadRED)") (class "Default")
      (node (ref "ESC2") (pin "RED") (pinfunction "RED_RED") (pintype "bidirectional"))
      (node (ref "ESC2_CON") (pin "C") (pinfunction "C_C") (pintype "bidirectional"))
    )
    (net (code "55") (name "Net-(ESC2-PadYEL)") (class "Default")
      (node (ref "ESC2") (pin "YEL") (pinfunction "YEL_YEL") (pintype "bidirectional"))
      (node (ref "ESC2_CON") (pin "B") (pinfunction "B_B") (pintype "bidirectional"))
    )
    (net (code "56") (name "Net-(ESC3-PadBLK)") (class "Default")
      (node (ref "ESC3") (pin "BLK") (pinfunction "BLK_BLK") (pintype "bidirectional"))
      (node (ref "ESC3_CON") (pin "A") (pinfunction "A_A") (pintype "bidirectional"))
    )
    (net (code "57") (name "Net-(ESC3-PadRED)") (class "Default")
      (node (ref "ESC3") (pin "RED") (pinfunction "RED_RED") (pintype "bidirectional"))
      (node (ref "ESC3_CON") (pin "C") (pinfunction "C_C") (pintype "bidirectional"))
    )
    (net (code "58") (name "Net-(ESC3-PadYEL)") (class "Default")
      (node (ref "ESC3") (pin "YEL") (pinfunction "YEL_YEL") (pintype "bidirectional"))
      (node (ref "ESC3_CON") (pin "B") (pinfunction "B_B") (pintype "bidirectional"))
    )
    (net (code "59") (name "Net-(R1-Pad1)") (class "Default")
      (node (ref "R1") (pin "1") (pinfunction "1_1") (pintype "passive"))
      (node (ref "U$2") (pin "FAULT") (pinfunction "FAULT_FAULT") (pintype "bidirectional"))
    )
    (net (code "60") (name "Net-(R2-Pad1)") (class "Default")
      (node (ref "R2") (pin "1") (pinfunction "1_1") (pintype "passive"))
      (node (ref "U$1") (pin "FAULT") (pinfunction "FAULT_FAULT") (pintype "bidirectional"))
    )
    (net (code "61") (name "Net-(R3-Pad1)") (class "Default")
      (node (ref "R3") (pin "1") (pinfunction "1_1") (pintype "passive"))
      (node (ref "U$3") (pin "FAULT") (pinfunction "FAULT_FAULT") (pintype "bidirectional"))
    )
    (net (code "62") (name "Net-(U2-PB6(XTAL1{slash}TOSC1))") (class "Default")
      (node (ref "C16") (pin "1") (pinfunction "1_1") (pintype "passive"))
      (node (ref "U2") (pin "7") (pinfunction "PB6(XTAL1/TOSC1)_7") (pintype "bidirectional"))
      (node (ref "Y2") (pin "2") (pinfunction "2_2") (pintype "passive"))
    )
    (net (code "63") (name "Net-(U2-PB7(XTAL2{slash}TOSC2))") (class "Default")
      (node (ref "C17") (pin "1") (pinfunction "1_1") (pintype "passive"))
      (node (ref "U2") (pin "8") (pinfunction "PB7(XTAL2/TOSC2)_8") (pintype "bidirectional"))
      (node (ref "Y2") (pin "1") (pinfunction "1_1") (pintype "passive"))
    )
    (net (code "64") (name "Net-(U4-#OE)") (class "Default")
      (node (ref "R15") (pin "2") (pinfunction "2_2") (pintype "passive"))
      (node (ref "U4") (pin "23") (pinfunction "#OE_23") (pintype "input"))
    )
    (net (code "65") (name "SCL") (class "Default")
      (node (ref "R22") (pin "1") (pinfunction "1_1") (pintype "passive"))
      (node (ref "R26") (pin "2") (pinfunction "2_2") (pintype "passive"))
      (node (ref "SV2") (pin "11") (pinfunction "11_11") (pintype "passive"))
      (node (ref "U$6") (pin "D") (pinfunction "D_D") (pintype "passive"))
      (node (ref "U2") (pin "28") (pinfunction "PC5(ADC5/SCL)_28") (pintype "bidirectional"))
    )
    (net (code "66") (name "SCL_PI") (class "Default")
      (node (ref "PCB1") (pin "P$5") (pinfunction "GPIO3_P$5") (pintype "bidirectional"))
      (node (ref "PS") (pin "P$2") (pinfunction "2_P$2") (pintype "passive"))
      (node (ref "R21") (pin "1") (pinfunction "1_1") (pintype "passive"))
      (node (ref "R26") (pin "1") (pinfunction "1_1") (pintype "passive"))
      (node (ref "U$5") (pin "SCL") (pinfunction "SCL_SCL") (pintype "bidirectional"))
      (node (ref "U$6") (pin "S") (pinfunction "S_S") (pintype "passive"))
      (node (ref "U4") (pin "26") (pinfunction "SCL_26") (pintype "bidirectional"))
    )
    (net (code "67") (name "SDA") (class "Default")
      (node (ref "R24") (pin "1") (pinfunction "1_1") (pintype "passive"))
      (node (ref "R25") (pin "2") (pinfunction "2_2") (pintype "passive"))
      (node (ref "SV2") (pin "12") (pinfunction "12_12") (pintype "passive"))
      (node (ref "U$7") (pin "D") (pinfunction "D_D") (pintype "passive"))
      (node (ref "U2") (pin "27") (pinfunction "PC4(ADC4/SDA)_27") (pintype "bidirectional"))
    )
    (net (code "68") (name "SDA_PI") (class "Default")
      (node (ref "PCB1") (pin "P$3") (pinfunction "GPIO2_P$3") (pintype "bidirectional"))
      (node (ref "PS") (pin "P$3") (pinfunction "3_P$3") (pintype "passive"))
      (node (ref "R23") (pin "1") (pinfunction "1_1") (pintype "passive"))
      (node (ref "R25") (pin "1") (pinfunction "1_1") (pintype "passive"))
      (node (ref "U$5") (pin "SDA") (pinfunction "SDA_SDA") (pintype "bidirectional"))
      (node (ref "U$7") (pin "S") (pinfunction "S_S") (pintype "passive"))
      (node (ref "U4") (pin "27") (pinfunction "SDA_27") (pintype "bidirectional"))
    )
    (net (code "69") (name "VCC") (class "Default")
      (node (ref "PCB1") (pin "P$2") (pinfunction "5V_P$2") (pintype "bidirectional"))
      (node (ref "PCB1") (pin "P$4") (pinfunction "5V_P$4") (pintype "bidirectional"))
      (node (ref "R19") (pin "2") (pinfunction "2_2") (pintype "passive"))
    )
    (net (code "70") (name "unconnected-(PCB1-3V3-PadP$1)") (class "Default")
      (node (ref "PCB1") (pin "P$1") (pinfunction "3V3_P$1") (pintype "bidirectional"))
    )
    (net (code "71") (name "unconnected-(PCB1-3V3-PadP$17)") (class "Default")
      (node (ref "PCB1") (pin "P$17") (pinfunction "3V3_P$17") (pintype "bidirectional"))
    )
    (net (code "72") (name "unconnected-(PCB1-GPIO4-PadP$7)") (class "Default")
      (node (ref "PCB1") (pin "P$7") (pinfunction "GPIO4_P$7") (pintype "bidirectional"))
    )
    (net (code "73") (name "unconnected-(PCB1-GPIO5-PadP$29)") (class "Default")
      (node (ref "PCB1") (pin "P$29") (pinfunction "GPIO5_P$29") (pintype "bidirectional"))
    )
    (net (code "74") (name "unconnected-(PCB1-GPIO6-PadP$31)") (class "Default")
      (node (ref "PCB1") (pin "P$31") (pinfunction "GPIO6_P$31") (pintype "bidirectional"))
    )
    (net (code "75") (name "unconnected-(PCB1-GPIO7-PadP$26)") (class "Default")
      (node (ref "PCB1") (pin "P$26") (pinfunction "GPIO7_P$26") (pintype "bidirectional"))
    )
    (net (code "76") (name "unconnected-(PCB1-GPIO8-PadP$24)") (class "Default")
      (node (ref "PCB1") (pin "P$24") (pinfunction "GPIO8_P$24") (pintype "bidirectional"))
    )
    (net (code "77") (name "unconnected-(PCB1-GPIO9-PadP$21)") (class "Default")
      (node (ref "PCB1") (pin "P$21") (pinfunction "GPIO9_P$21") (pintype "bidirectional"))
    )
    (net (code "78") (name "unconnected-(PCB1-GPIO10-PadP$19)") (class "Default")
      (node (ref "PCB1") (pin "P$19") (pinfunction "GPIO10_P$19") (pintype "bidirectional"))
    )
    (net (code "79") (name "unconnected-(PCB1-GPIO11-PadP$23)") (class "Default")
      (node (ref "PCB1") (pin "P$23") (pinfunction "GPIO11_P$23") (pintype "bidirectional"))
    )
    (net (code "80") (name "unconnected-(PCB1-GPIO12-PadP$32)") (class "Default")
      (node (ref "PCB1") (pin "P$32") (pinfunction "GPIO12_P$32") (pintype "bidirectional"))
    )
    (net (code "81") (name "unconnected-(PCB1-GPIO13-PadP$33)") (class "Default")
      (node (ref "PCB1") (pin "P$33") (pinfunction "GPIO13_P$33") (pintype "bidirectional"))
    )
    (net (code "82") (name "unconnected-(PCB1-GPIO16-PadP$36)") (class "Default")
      (node (ref "PCB1") (pin "P$36") (pinfunction "GPIO16_P$36") (pintype "bidirectional"))
    )
    (net (code "83") (name "unconnected-(PCB1-GPIO17-PadP$11)") (class "Default")
      (node (ref "PCB1") (pin "P$11") (pinfunction "GPIO17_P$11") (pintype "bidirectional"))
    )
    (net (code "84") (name "unconnected-(PCB1-GPIO19-PadP$35)") (class "Default")
      (node (ref "PCB1") (pin "P$35") (pinfunction "GPIO19_P$35") (pintype "bidirectional"))
    )
    (net (code "85") (name "unconnected-(PCB1-GPIO20-PadP$38)") (class "Default")
      (node (ref "PCB1") (pin "P$38") (pinfunction "GPIO20_P$38") (pintype "bidirectional"))
    )
    (net (code "86") (name "unconnected-(PCB1-GPIO21-PadP$40)") (class "Default")
      (node (ref "PCB1") (pin "P$40") (pinfunction "GPIO21_P$40") (pintype "bidirectional"))
    )
    (net (code "87") (name "unconnected-(PCB1-GPIO22-PadP$15)") (class "Default")
      (node (ref "PCB1") (pin "P$15") (pinfunction "GPIO22_P$15") (pintype "bidirectional"))
    )
    (net (code "88") (name "unconnected-(PCB1-GPIO23-PadP$16)") (class "Default")
      (node (ref "PCB1") (pin "P$16") (pinfunction "GPIO23_P$16") (pintype "bidirectional"))
    )
    (net (code "89") (name "unconnected-(PCB1-GPIO24-PadP$18)") (class "Default")
      (node (ref "PCB1") (pin "P$18") (pinfunction "GPIO24_P$18") (pintype "bidirectional"))
    )
    (net (code "90") (name "unconnected-(PCB1-GPIO25-PadP$22)") (class "Default")
      (node (ref "PCB1") (pin "P$22") (pinfunction "GPIO25_P$22") (pintype "bidirectional"))
    )
    (net (code "91") (name "unconnected-(PCB1-GPIO26-PadP$37)") (class "Default")
      (node (ref "PCB1") (pin "P$37") (pinfunction "GPIO26_P$37") (pintype "bidirectional"))
    )
    (net (code "92") (name "unconnected-(PCB1-GPIO27-PadP$13)") (class "Default")
      (node (ref "PCB1") (pin "P$13") (pinfunction "GPIO27_P$13") (pintype "bidirectional"))
    )
    (net (code "93") (name "unconnected-(PCB1-ID_SC*-PadP$28)") (class "Default")
      (node (ref "PCB1") (pin "P$28") (pinfunction "ID_SC*_P$28") (pintype "bidirectional"))
    )
    (net (code "94") (name "unconnected-(PCB1-ID_SD*-PadP$27)") (class "Default")
      (node (ref "PCB1") (pin "P$27") (pinfunction "ID_SD*_P$27") (pintype "bidirectional"))
    )
    (net (code "95") (name "unconnected-(U$4-PadCH0)") (class "Default")
      (node (ref "U$4") (pin "CH0") (pinfunction "CH0_CH0") (pintype "bidirectional"))
    )
    (net (code "96") (name "unconnected-(U$4-PadCH7)") (class "Default")
      (node (ref "U$4") (pin "CH7") (pinfunction "CH7_CH7") (pintype "bidirectional"))
    )
    (net (code "97") (name "unconnected-(U$5-Pad3VO)") (class "Default")
      (node (ref "U$5") (pin "3VO") (pinfunction "3VO_3VO") (pintype "bidirectional"))
    )
    (net (code "98") (name "unconnected-(U$5-PadADR)") (class "Default")
      (node (ref "U$5") (pin "ADR") (pinfunction "ADR_ADR") (pintype "bidirectional"))
    )
    (net (code "99") (name "unconnected-(U$5-PadINT)") (class "Default")
      (node (ref "U$5") (pin "INT") (pinfunction "INT_INT") (pintype "bidirectional"))
    )
    (net (code "100") (name "unconnected-(U$5-PadPS0)") (class "Default")
      (node (ref "U$5") (pin "PS0") (pinfunction "PS0_PS0") (pintype "bidirectional"))
    )
    (net (code "101") (name "unconnected-(U$5-PadPS1)") (class "Default")
      (node (ref "U$5") (pin "PS1") (pinfunction "PS1_PS1") (pintype "bidirectional"))
    )
    (net (code "102") (name "unconnected-(U$5-PadRST)") (class "Default")
      (node (ref "U$5") (pin "RST") (pinfunction "RST_RST") (pintype "bidirectional"))
    )
    (net (code "103") (name "unconnected-(U2-ADC6-Pad19)") (class "Default")
      (node (ref "U2") (pin "19") (pinfunction "ADC6_19") (pintype "bidirectional"))
    )
    (net (code "104") (name "unconnected-(U2-ADC7-Pad22)") (class "Default")
      (node (ref "U2") (pin "22") (pinfunction "ADC7_22") (pintype "bidirectional"))
    )
    (net (code "105") (name "unconnected-(U2-PB1(OC1A)-Pad13)") (class "Default")
      (node (ref "U2") (pin "13") (pinfunction "PB1(OC1A)_13") (pintype "bidirectional"))
    )
    (net (code "106") (name "unconnected-(U2-PC0(ADC0)-Pad23)") (class "Default")
      (node (ref "U2") (pin "23") (pinfunction "PC0(ADC0)_23") (pintype "bidirectional"))
    )
    (net (code "107") (name "unconnected-(U2-PC1(ADC1)-Pad24)") (class "Default")
      (node (ref "U2") (pin "24") (pinfunction "PC1(ADC1)_24") (pintype "bidirectional"))
    )
    (net (code "108") (name "unconnected-(U2-PC2(ADC2)-Pad25)") (class "Default")
      (node (ref "U2") (pin "25") (pinfunction "PC2(ADC2)_25") (pintype "bidirectional"))
    )
    (net (code "109") (name "unconnected-(U2-PC3(ADC3)-Pad26)") (class "Default")
      (node (ref "U2") (pin "26") (pinfunction "PC3(ADC3)_26") (pintype "bidirectional"))
    )
    (net (code "110") (name "unconnected-(U2-PD0(RXD)-Pad30)") (class "Default")
      (node (ref "U2") (pin "30") (pinfunction "PD0(RXD)_30") (pintype "bidirectional"))
    )
    (net (code "111") (name "unconnected-(U2-PD1(TXD)-Pad31)") (class "Default")
      (node (ref "U2") (pin "31") (pinfunction "PD1(TXD)_31") (pintype "bidirectional"))
    )
    (net (code "112") (name "unconnected-(U2-PD2(INT0)-Pad32)") (class "Default")
      (node (ref "U2") (pin "32") (pinfunction "PD2(INT0)_32") (pintype "bidirectional"))
    )
  )
)
